# sensor_output.net
KiCad netlist of a schematic drawn in Altium Designer
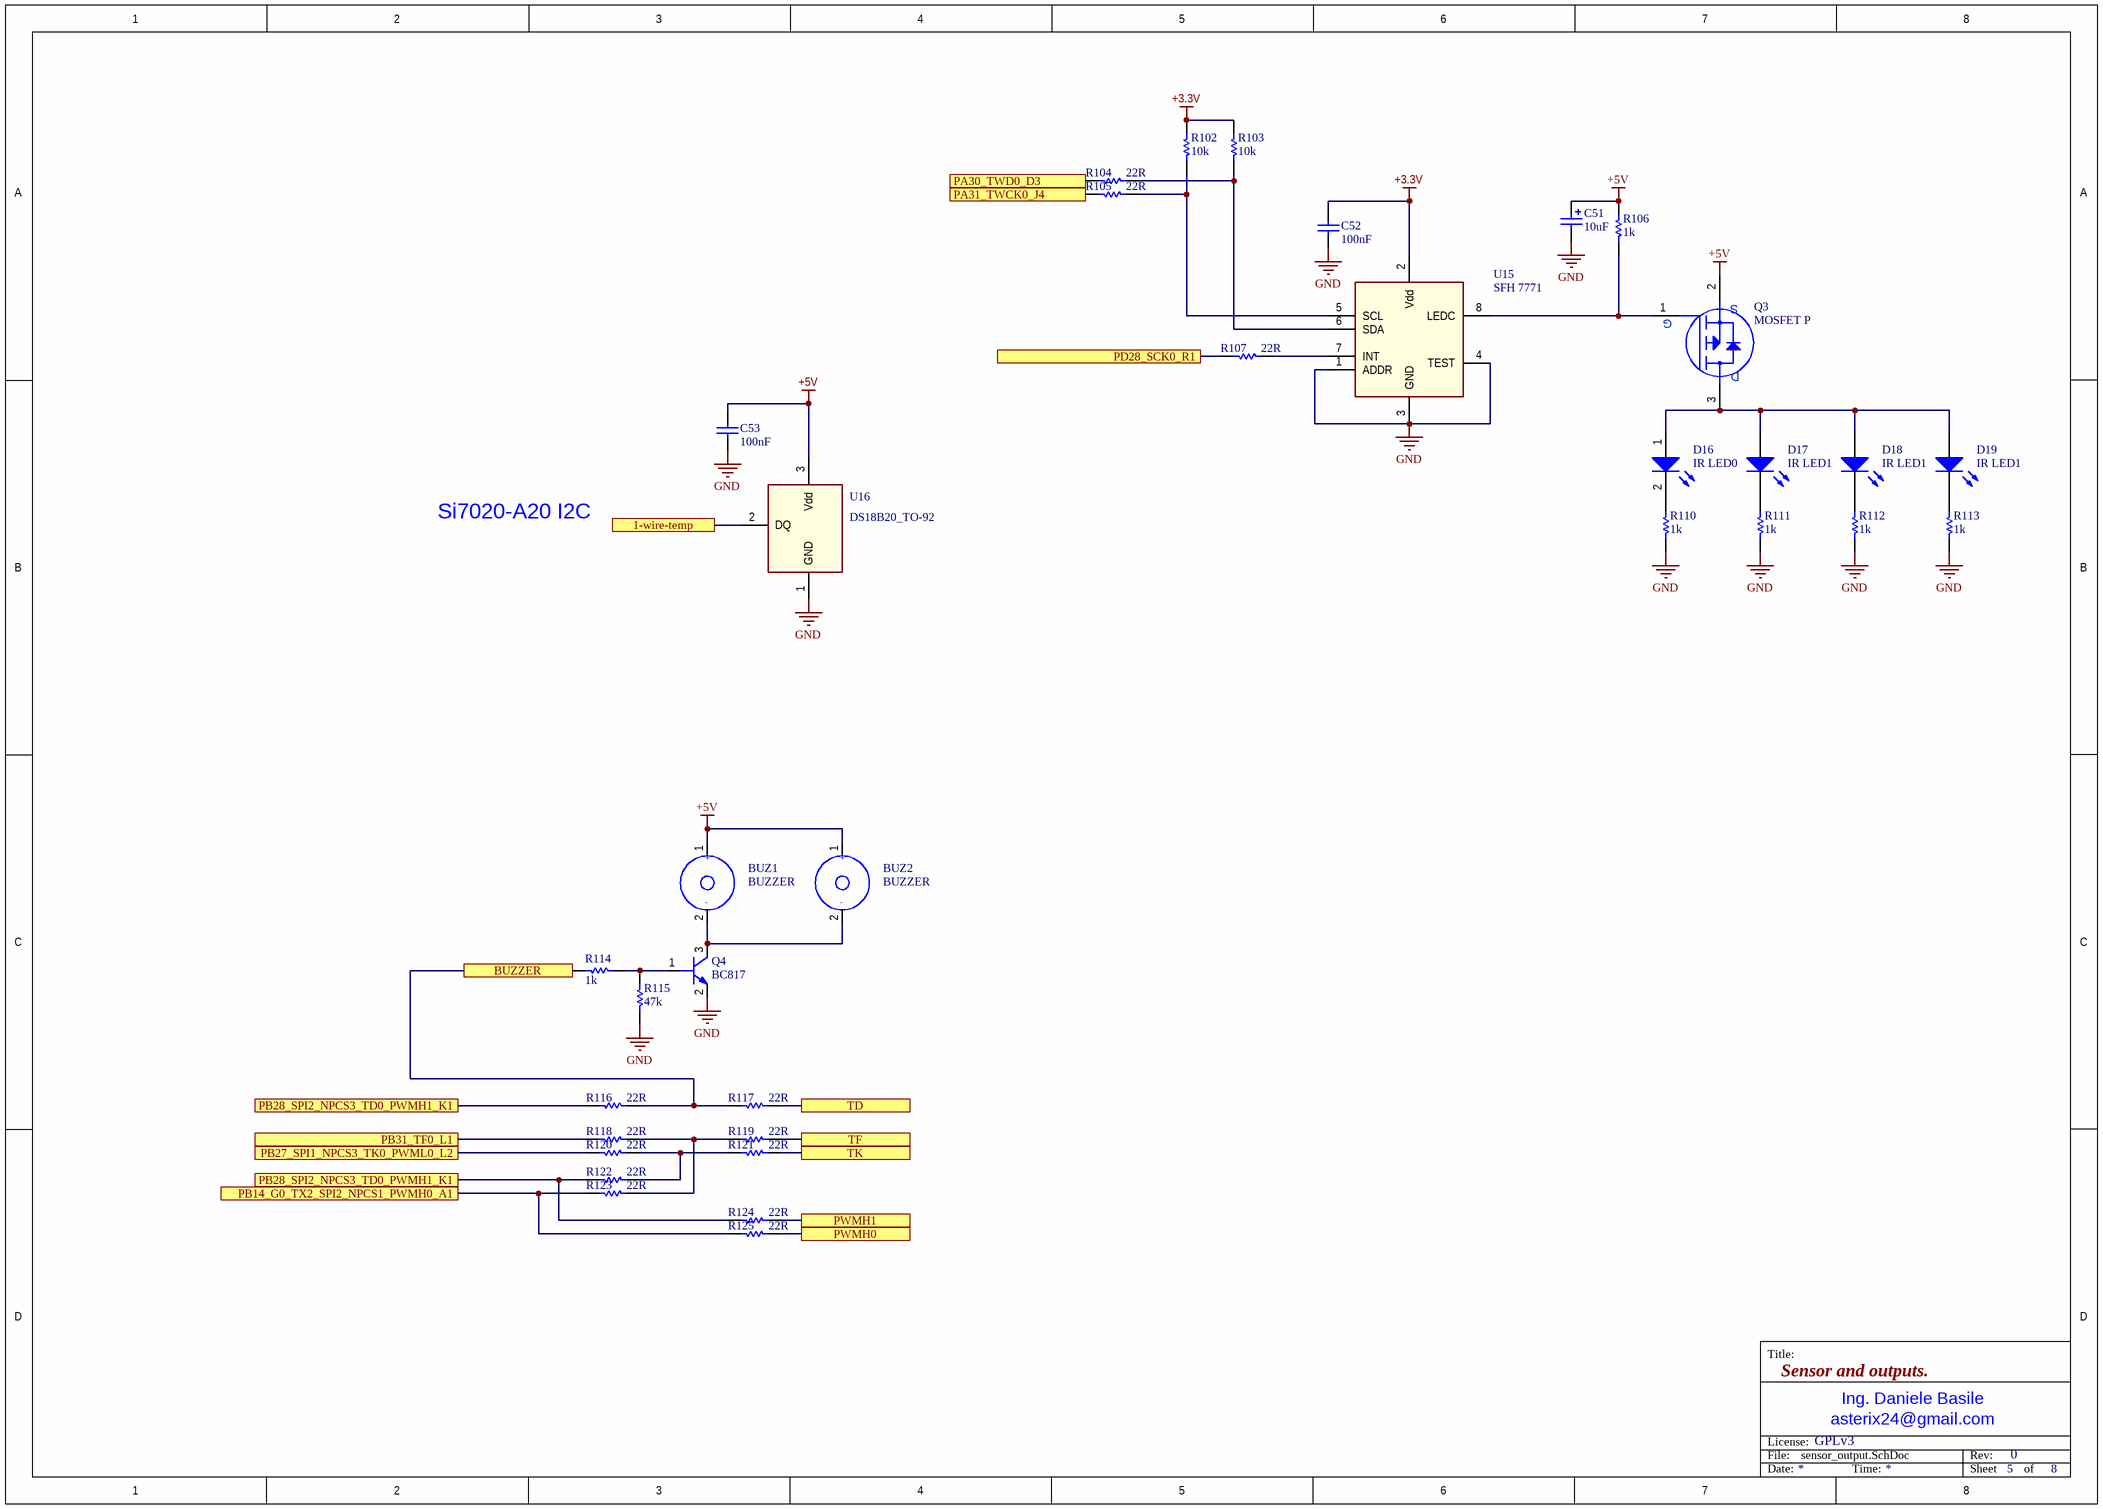
[diagram p0: sensor_output.SchDoc]

(export (version "E")
  (design (tool "Eeschema 10.0.6"))
  (components
    (comp (ref "BUZ1")
      (value "BUZZER")
      (footprint "buzzer_14mm_thd")
      (libsource (lib "develer_library") (part "BUZZER"))
    )
    (comp (ref "BUZ2")
      (value "BUZZER")
      (footprint "BUZZER_9x9MM_SMD")
      (libsource (lib "develer_library") (part "BUZZER"))
    )
    (comp (ref "C51")
      (value "10uF")
      (footprint "1206_[3216]")
      (description "Ceramic X5R 25V")
      (fields (field (name "PUBLISHER") "Altium Limited"))
      (libsource (lib "DEVELER_Library") (part "Cap Pol1"))
    )
    (comp (ref "C52")
      (value "100nF")
      (footprint "0603_[1608]")
      (description "Ceramic X7R 50V")
      (fields (field (name "PUBLISHER") "Altium Limited"))
      (libsource (lib "DEVELER_Library") (part "Cap"))
    )
    (comp (ref "C53")
      (value "100nF")
      (footprint "0603_[1608]")
      (description "Ceramic X7R 50V")
      (fields (field (name "PUBLISHER") "Altium Limited"))
      (libsource (lib "DEVELER_Library") (part "Cap"))
    )
    (comp (ref "D16")
      (value "IR LED0")
      (footprint "0603_[1608]_K2-A1_LED")
      (description "LED Green")
      (fields (field (name "PUBLISHER") "Altium Limited"))
      (libsource (lib "") (part "LED0_1"))
    )
    (comp (ref "D17")
      (value "IR LED1")
      (footprint "0603_[1608]_K2-A1_LED")
      (description "LED Green")
      (fields (field (name "PUBLISHER") "Altium Limited"))
      (libsource (lib "DEVELER_Library") (part "LED0"))
    )
    (comp (ref "D18")
      (value "IR LED1")
      (footprint "0603_[1608]_K2-A1_LED")
      (description "LED Green")
      (fields (field (name "PUBLISHER") "Altium Limited"))
      (libsource (lib "DEVELER_Library") (part "LED0"))
    )
    (comp (ref "D19")
      (value "IR LED1")
      (footprint "0603_[1608]_K2-A1_LED")
      (description "LED Green")
      (fields (field (name "PUBLISHER") "Altium Limited"))
      (libsource (lib "DEVELER_Library") (part "LED0"))
    )
    (comp (ref "Q3")
      (value "MOSFET P")
      (footprint "SOT-23")
      (description "MOSFET channel P")
      (libsource (lib "develer_library") (part "MOSFET-P 3pin"))
    )
    (comp (ref "Q4")
      (value "BC817")
      (footprint "SOT-23")
      (description "BJT NPN")
      (libsource (lib "develer_library") (part "BC817"))
    )
    (comp (ref "R102")
      (value "10k")
      (footprint "0603_[1608]")
      (description "Resistor")
      (libsource (lib "DEVELER_Library") (part "Res1"))
    )
    (comp (ref "R103")
      (value "10k")
      (footprint "0603_[1608]")
      (description "Resistor")
      (libsource (lib "DEVELER_Library") (part "Res1"))
    )
    (comp (ref "R104")
      (value "22R")
      (footprint "0603_[1608]")
      (description "Resistor")
      (libsource (lib "DEVELER_Library") (part "Res1"))
    )
    (comp (ref "R105")
      (value "22R")
      (footprint "0603_[1608]")
      (description "Resistor")
      (libsource (lib "DEVELER_Library") (part "Res1"))
    )
    (comp (ref "R106")
      (value "1k")
      (footprint "0603_[1608]")
      (description "Resistor")
      (libsource (lib "DEVELER_Library") (part "Res1"))
    )
    (comp (ref "R107")
      (value "22R")
      (footprint "0603_[1608]")
      (description "Resistor")
      (libsource (lib "DEVELER_Library") (part "Res1"))
    )
    (comp (ref "R110")
      (value "1k")
      (footprint "0603_[1608]")
      (description "Resistor")
      (libsource (lib "DEVELER_Library") (part "Res1"))
    )
    (comp (ref "R111")
      (value "1k")
      (footprint "0603_[1608]")
      (description "Resistor")
      (libsource (lib "DEVELER_Library") (part "Res1"))
    )
    (comp (ref "R112")
      (value "1k")
      (footprint "0603_[1608]")
      (description "Resistor")
      (libsource (lib "DEVELER_Library") (part "Res1"))
    )
    (comp (ref "R113")
      (value "1k")
      (footprint "0603_[1608]")
      (description "Resistor")
      (libsource (lib "DEVELER_Library") (part "Res1"))
    )
    (comp (ref "R114")
      (value "1k")
      (footprint "0603_[1608]")
      (description "Resistor")
      (fields (field (name "PUBLISHER") "Altium Limited"))
      (libsource (lib "") (part "Res1_1"))
    )
    (comp (ref "R115")
      (value "47k")
      (footprint "0603_[1608]")
      (description "Resistor")
      (fields (field (name "PUBLISHER") "Altium Limited"))
      (libsource (lib "") (part "Res1_1"))
    )
    (comp (ref "R116")
      (value "22R")
      (footprint "0603_[1608]")
      (description "Resistor")
      (libsource (lib "DEVELER_Library") (part "Res1"))
    )
    (comp (ref "R117")
      (value "22R")
      (footprint "0603_[1608]")
      (description "Resistor")
      (libsource (lib "DEVELER_Library") (part "Res1"))
    )
    (comp (ref "R118")
      (value "22R")
      (footprint "0603_[1608]")
      (description "Resistor")
      (libsource (lib "DEVELER_Library") (part "Res1"))
    )
    (comp (ref "R119")
      (value "22R")
      (footprint "0603_[1608]")
      (description "Resistor")
      (libsource (lib "DEVELER_Library") (part "Res1"))
    )
    (comp (ref "R120")
      (value "22R")
      (footprint "0603_[1608]")
      (description "Resistor")
      (libsource (lib "DEVELER_Library") (part "Res1"))
    )
    (comp (ref "R121")
      (value "22R")
      (footprint "0603_[1608]")
      (description "Resistor")
      (libsource (lib "DEVELER_Library") (part "Res1"))
    )
    (comp (ref "R122")
      (value "22R")
      (footprint "0603_[1608]")
      (description "Resistor")
      (libsource (lib "DEVELER_Library") (part "Res1"))
    )
    (comp (ref "R123")
      (value "22R")
      (footprint "0603_[1608]")
      (description "Resistor")
      (libsource (lib "DEVELER_Library") (part "Res1"))
    )
    (comp (ref "R124")
      (value "22R")
      (footprint "0603_[1608]")
      (description "Resistor")
      (libsource (lib "DEVELER_Library") (part "Res1"))
    )
    (comp (ref "R125")
      (value "22R")
      (footprint "0603_[1608]")
      (description "Resistor")
      (libsource (lib "DEVELER_Library") (part "Res1"))
    )
    (comp (ref "U15")
      (value "SFH 7771")
      (footprint "QFN_SFH7771")
      (description "OSRAM Integrated Ambient Light and Proximity Sensors")
      (libsource (lib "develer_library") (part "SFH 7771"))
    )
    (comp (ref "U16")
      (value "DS18B20_TO-92")
      (footprint "develer_misc:TO-92")
      (description "1-Wire temperature sensor.")
      (libsource (lib "develer_library") (part "DS18B20_TO-92"))
    )
  )
  (nets
    (net (code "1") (name "+3.3V") (class "Default")
      (node (ref "C52") (pin "2") (pinfunction "2_2") (pintype "passive"))
      (node (ref "R102") (pin "1") (pinfunction "1_1") (pintype "passive"))
      (node (ref "R103") (pin "1") (pinfunction "1_1") (pintype "passive"))
      (node (ref "U15") (pin "2") (pinfunction "Vdd_2") (pintype "passive"))
    )
    (net (code "2") (name "+5V") (class "Default")
      (node (ref "BUZ1") (pin "1") (pinfunction "1_1") (pintype "bidirectional"))
      (node (ref "BUZ2") (pin "1") (pinfunction "1_1") (pintype "bidirectional"))
      (node (ref "C51") (pin "1") (pinfunction "1_1") (pintype "passive"))
      (node (ref "C53") (pin "2") (pinfunction "2_2") (pintype "passive"))
      (node (ref "Q3") (pin "2") (pinfunction "S_2") (pintype "passive"))
      (node (ref "R106") (pin "1") (pinfunction "1_1") (pintype "passive"))
      (node (ref "U16") (pin "3") (pinfunction "Vdd_3") (pintype "passive"))
    )
    (net (code "3") (name "/1-wire-temp") (class "Default")
      (node (ref "U16") (pin "2") (pinfunction "DQ_2") (pintype "passive"))
    )
    (net (code "4") (name "/BUZZER") (class "Default")
      (node (ref "R114") (pin "2") (pinfunction "2_2") (pintype "passive"))
      (node (ref "R116") (pin "1") (pinfunction "1_1") (pintype "passive"))
      (node (ref "R117") (pin "2") (pinfunction "2_2") (pintype "passive"))
    )
    (net (code "5") (name "/PA30_TWD0_D3") (class "Default")
      (node (ref "R104") (pin "2") (pinfunction "2_2") (pintype "passive"))
    )
    (net (code "6") (name "/PA31_TWCK0_J4") (class "Default")
      (node (ref "R105") (pin "2") (pinfunction "2_2") (pintype "passive"))
    )
    (net (code "7") (name "/PB14_G0_TX2_SPI2_NPCS1_PWMH0_A1") (class "Default")
      (node (ref "R123") (pin "2") (pinfunction "2_2") (pintype "passive"))
      (node (ref "R125") (pin "2") (pinfunction "2_2") (pintype "passive"))
    )
    (net (code "8") (name "/PB27_SPI1_NPCS3_TK0_PWML0_L2") (class "Default")
      (node (ref "R120") (pin "2") (pinfunction "2_2") (pintype "passive"))
    )
    (net (code "9") (name "/PB28_SPI2_NPCS3_TD0_PWMH1_K1") (class "Default")
      (node (ref "R116") (pin "2") (pinfunction "2_2") (pintype "passive"))
      (node (ref "R122") (pin "2") (pinfunction "2_2") (pintype "passive"))
      (node (ref "R124") (pin "2") (pinfunction "2_2") (pintype "passive"))
    )
    (net (code "10") (name "/PB31_TF0_L1") (class "Default")
      (node (ref "R118") (pin "2") (pinfunction "2_2") (pintype "passive"))
    )
    (net (code "11") (name "/PD28_SCK0_R1") (class "Default")
      (node (ref "R107") (pin "2") (pinfunction "2_2") (pintype "passive"))
    )
    (net (code "12") (name "/PWMH0") (class "Default")
      (node (ref "R125") (pin "1") (pinfunction "1_1") (pintype "passive"))
    )
    (net (code "13") (name "/PWMH1") (class "Default")
      (node (ref "R124") (pin "1") (pinfunction "1_1") (pintype "passive"))
    )
    (net (code "14") (name "/TD") (class "Default")
      (node (ref "R117") (pin "1") (pinfunction "1_1") (pintype "passive"))
    )
    (net (code "15") (name "/TF") (class "Default")
      (node (ref "R119") (pin "1") (pinfunction "1_1") (pintype "passive"))
    )
    (net (code "16") (name "/TK") (class "Default")
      (node (ref "R121") (pin "1") (pinfunction "1_1") (pintype "passive"))
    )
    (net (code "17") (name "GND") (class "Default")
      (node (ref "C51") (pin "2") (pinfunction "2_2") (pintype "passive"))
      (node (ref "C52") (pin "1") (pinfunction "1_1") (pintype "passive"))
      (node (ref "C53") (pin "1") (pinfunction "1_1") (pintype "passive"))
      (node (ref "Q4") (pin "2") (pinfunction "E_2") (pintype "passive"))
      (node (ref "R110") (pin "2") (pinfunction "2_2") (pintype "passive"))
      (node (ref "R111") (pin "2") (pinfunction "2_2") (pintype "passive"))
      (node (ref "R112") (pin "2") (pinfunction "2_2") (pintype "passive"))
      (node (ref "R113") (pin "2") (pinfunction "2_2") (pintype "passive"))
      (node (ref "R115") (pin "2") (pinfunction "2_2") (pintype "passive"))
      (node (ref "U15") (pin "1") (pinfunction "ADDR_1") (pintype "passive"))
      (node (ref "U15") (pin "3") (pinfunction "GND_3") (pintype "passive"))
      (node (ref "U15") (pin "4") (pinfunction "TEST_4") (pintype "passive"))
      (node (ref "U16") (pin "1") (pinfunction "GND_1") (pintype "passive"))
    )
    (net (code "18") (name "Net-(D16-A)") (class "Default")
      (node (ref "D16") (pin "1") (pinfunction "A_1") (pintype "passive"))
      (node (ref "D17") (pin "1") (pinfunction "A_1") (pintype "passive"))
      (node (ref "D18") (pin "1") (pinfunction "A_1") (pintype "passive"))
      (node (ref "D19") (pin "1") (pinfunction "A_1") (pintype "passive"))
      (node (ref "Q3") (pin "3") (pinfunction "D_3") (pintype "passive"))
    )
    (net (code "19") (name "Net-(D16-K)") (class "Default")
      (node (ref "D16") (pin "2") (pinfunction "K_2") (pintype "passive"))
      (node (ref "R110") (pin "1") (pinfunction "1_1") (pintype "passive"))
    )
    (net (code "20") (name "Net-(D17-K)") (class "Default")
      (node (ref "D17") (pin "2") (pinfunction "K_2") (pintype "passive"))
      (node (ref "R111") (pin "1") (pinfunction "1_1") (pintype "passive"))
    )
    (net (code "21") (name "Net-(D18-K)") (class "Default")
      (node (ref "D18") (pin "2") (pinfunction "K_2") (pintype "passive"))
      (node (ref "R112") (pin "1") (pinfunction "1_1") (pintype "passive"))
    )
    (net (code "22") (name "Net-(D19-K)") (class "Default")
      (node (ref "D19") (pin "2") (pinfunction "K_2") (pintype "passive"))
      (node (ref "R113") (pin "1") (pinfunction "1_1") (pintype "passive"))
    )
    (net (code "23") (name "Net-(Q3-G)") (class "Default")
      (node (ref "Q3") (pin "1") (pinfunction "G_1") (pintype "passive"))
      (node (ref "R106") (pin "2") (pinfunction "2_2") (pintype "passive"))
      (node (ref "U15") (pin "8") (pinfunction "LEDC_8") (pintype "passive"))
    )
    (net (code "24") (name "Net-(Q4-B)") (class "Default")
      (node (ref "Q4") (pin "1") (pinfunction "B_1") (pintype "passive"))
      (node (ref "R114") (pin "1") (pinfunction "1_1") (pintype "passive"))
      (node (ref "R115") (pin "1") (pinfunction "1_1") (pintype "passive"))
    )
    (net (code "25") (name "Net-(Q4-C)") (class "Default")
      (node (ref "BUZ1") (pin "2") (pinfunction "2_2") (pintype "bidirectional"))
      (node (ref "BUZ2") (pin "2") (pinfunction "2_2") (pintype "bidirectional"))
      (node (ref "Q4") (pin "3") (pinfunction "C_3") (pintype "passive"))
    )
    (net (code "26") (name "Net-(R118-Pad1)") (class "Default")
      (node (ref "R118") (pin "1") (pinfunction "1_1") (pintype "passive"))
      (node (ref "R119") (pin "2") (pinfunction "2_2") (pintype "passive"))
      (node (ref "R123") (pin "1") (pinfunction "1_1") (pintype "passive"))
    )
    (net (code "27") (name "Net-(R120-Pad1)") (class "Default")
      (node (ref "R120") (pin "1") (pinfunction "1_1") (pintype "passive"))
      (node (ref "R121") (pin "2") (pinfunction "2_2") (pintype "passive"))
      (node (ref "R122") (pin "1") (pinfunction "1_1") (pintype "passive"))
    )
    (net (code "28") (name "Net-(U15-INT)") (class "Default")
      (node (ref "R107") (pin "1") (pinfunction "1_1") (pintype "passive"))
      (node (ref "U15") (pin "7") (pinfunction "INT_7") (pintype "passive"))
    )
    (net (code "29") (name "Net-(U15-SCL)") (class "Default")
      (node (ref "R102") (pin "2") (pinfunction "2_2") (pintype "passive"))
      (node (ref "R105") (pin "1") (pinfunction "1_1") (pintype "passive"))
      (node (ref "U15") (pin "5") (pinfunction "SCL_5") (pintype "passive"))
    )
    (net (code "30") (name "Net-(U15-SDA)") (class "Default")
      (node (ref "R103") (pin "2") (pinfunction "2_2") (pintype "passive"))
      (node (ref "R104") (pin "1") (pinfunction "1_1") (pintype "passive"))
      (node (ref "U15") (pin "6") (pinfunction "SDA_6") (pintype "passive"))
    )
  )
)
